# CAN.net
KiCad netlist of a schematic drawn in Altium Designer
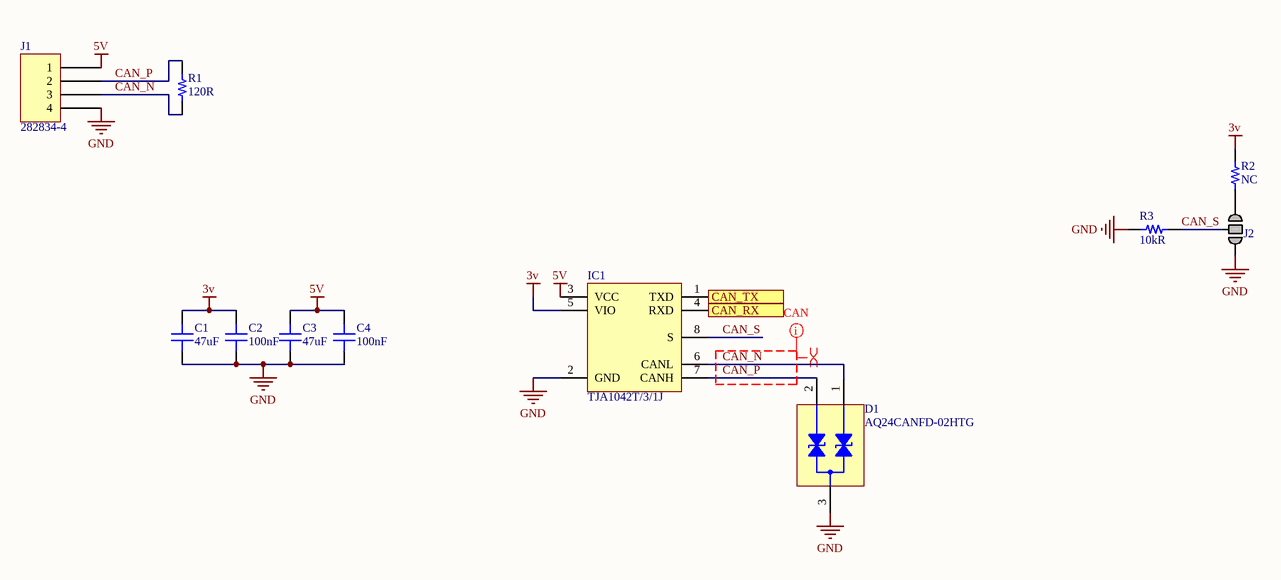
[diagram p0: CAN.SchDoc]

(export (version "E")
  (design (tool "Eeschema 10.0.6"))
  (components
    (comp (ref "C1")
      (value "47uF")
      (footprint "CAP 0603/1608")
      (description "Ceramic, SMT Capacitor")
      (fields
        (field (name "MANUFACTURER") "Murata")
        (field (name "MANUFACTURER PART NUMBER") "GRM188C80E476ME05D")
      )
      (libsource (lib "yildizIoT Library") (part "Capacitor - Ceramic"))
    )
    (comp (ref "C2")
      (value "100nF")
      (footprint "CAP 0603/1608")
      (description "Ceramic, SMT Capacitor")
      (fields
        (field (name "MANUFACTURER") "KEMET")
        (field (name "MANUFACTURER PART NUMBER") "C0603C104Z3VACTU")
      )
      (libsource (lib "yildizIoT Library") (part "Capacitor - Ceramic"))
    )
    (comp (ref "C3")
      (value "47uF")
      (footprint "CAP 0603/1608")
      (description "Ceramic, SMT Capacitor")
      (fields
        (field (name "MANUFACTURER") "Murata")
        (field (name "MANUFACTURER PART NUMBER") "GRM188C80E476ME05D")
      )
      (libsource (lib "yildizIoT Library") (part "Capacitor - Ceramic"))
    )
    (comp (ref "C4")
      (value "100nF")
      (footprint "CAP 0603/1608")
      (description "Ceramic, SMT Capacitor")
      (fields
        (field (name "MANUFACTURER") "KEMET")
        (field (name "MANUFACTURER PART NUMBER") "C0603C104Z3VACTU")
      )
      (libsource (lib "yildizIoT Library") (part "Capacitor - Ceramic"))
    )
    (comp (ref "D1")
      (value "AQ24CANFD-02HTG")
      (footprint "ON SEMI SOT-23-3")
      (description "TVS DIODE 24V 44V SOT23-3")
      (fields (field (name "MANUFACTURER") "Littelfuse"))
      (libsource (lib "Celestial Altium Library - altium_library") (part "ON SEMI SOT-23-3"))
    )
    (comp (ref "IC1")
      (value "TJA1042T/3/1J")
      (footprint "NXP SOIC-8")
      (description "High Speed CAN, CAN FD Transceiver")
      (fields (field (name "MANUFACTURER") "NXP Semiconductors"))
      (libsource (lib "yildizIoT Library") (part "NXP TJA1042T_3_1J"))
    )
    (comp (ref "J1")
      (value "282834-4")
      (footprint "TE 282834-4")
      (description "TERM BLK 4P SIDE ENT 2.54MM PCB")
      (fields (field (name "MANUFACTURER") "TE Connectivity AMP Connectors") (field (name "VOLTAGE") "150V"))
      (libsource (lib "Celestial Altium Library - altium_library") (part "4 Pin"))
    )
    (comp (ref "J2")
      (value "~")
      (footprint "jump_3way")
      (description "Selectable jumber")
      (libsource (lib "Muhammet_All_In_One") (part "JUMPER"))
    )
    (comp (ref "R1")
      (value "120R")
      (footprint "RES 0603/1608")
      (description "Ceramic, SMT Capacitor")
      (fields
        (field (name "MANUFACTURER") "Susumu")
        (field (name "MANUFACTURER PART NUMBER") "RR0816P-121-D")
      )
      (libsource (lib "yildizIoT Library") (part "Resistor_Chip"))
    )
    (comp (ref "R2")
      (value "NC")
      (footprint "RES 0603/1608")
      (description "Ceramic, SMT Capacitor")
      (libsource (lib "yildizIoT Library") (part "Resistor_Chip"))
    )
    (comp (ref "R3")
      (value "10kR")
      (footprint "RES 0603/1608")
      (description "Ceramic, SMT Capacitor")
      (fields
        (field (name "MANUFACTURER") "Stackpole Electronics")
        (field (name "MANUFACTURER PART NUMBER") "RNCP0603FTD10K0")
      )
      (libsource (lib "yildizIoT Library") (part "Resistor_Chip"))
    )
  )
  (nets
    (net (code "1") (name "/CAN_N") (class "Default")
      (node (ref "D1") (pin "1") (pinfunction "I/O_1_1") (pintype "passive"))
      (node (ref "IC1") (pin "6") (pinfunction "CANL_6") (pintype "passive"))
      (node (ref "J1") (pin "3") (pinfunction "3_3") (pintype "passive"))
      (node (ref "R1") (pin "1") (pinfunction "1_1") (pintype "passive"))
    )
    (net (code "2") (name "/CAN_P") (class "Default")
      (node (ref "D1") (pin "2") (pinfunction "GND_2") (pintype "passive"))
      (node (ref "IC1") (pin "7") (pinfunction "CANH_7") (pintype "passive"))
      (node (ref "J1") (pin "2") (pinfunction "2_2") (pintype "passive"))
      (node (ref "R1") (pin "2") (pinfunction "2_2") (pintype "passive"))
    )
    (net (code "3") (name "/CAN_RX") (class "Default")
      (node (ref "IC1") (pin "4") (pinfunction "RXD_4") (pintype "passive"))
    )
    (net (code "4") (name "/CAN_S") (class "Default")
      (node (ref "IC1") (pin "8") (pinfunction "S_8") (pintype "passive"))
      (node (ref "J2") (pin "2") (pinfunction "2_2") (pintype "passive"))
      (node (ref "R3") (pin "2") (pinfunction "2_2") (pintype "passive"))
    )
    (net (code "5") (name "/CAN_TX") (class "Default")
      (node (ref "IC1") (pin "1") (pinfunction "TXD_1") (pintype "passive"))
    )
    (net (code "6") (name "3v") (class "Default")
      (node (ref "C1") (pin "2") (pinfunction "2_2") (pintype "passive"))
      (node (ref "C2") (pin "2") (pinfunction "2_2") (pintype "passive"))
      (node (ref "IC1") (pin "5") (pinfunction "VIO_5") (pintype "passive"))
      (node (ref "R2") (pin "1") (pinfunction "1_1") (pintype "passive"))
    )
    (net (code "7") (name "5V") (class "Default")
      (node (ref "C3") (pin "2") (pinfunction "2_2") (pintype "passive"))
      (node (ref "C4") (pin "2") (pinfunction "2_2") (pintype "passive"))
      (node (ref "IC1") (pin "3") (pinfunction "VCC_3") (pintype "passive"))
      (node (ref "J1") (pin "1") (pinfunction "1_1") (pintype "passive"))
    )
    (net (code "8") (name "GND") (class "Default")
      (node (ref "C1") (pin "1") (pinfunction "1_1") (pintype "passive"))
      (node (ref "C2") (pin "1") (pinfunction "1_1") (pintype "passive"))
      (node (ref "C3") (pin "1") (pinfunction "1_1") (pintype "passive"))
      (node (ref "C4") (pin "1") (pinfunction "1_1") (pintype "passive"))
      (node (ref "D1") (pin "3") (pinfunction "I/O_2_3") (pintype "passive"))
      (node (ref "IC1") (pin "2") (pinfunction "GND_2") (pintype "passive"))
      (node (ref "J1") (pin "4") (pinfunction "4_4") (pintype "passive"))
      (node (ref "J2") (pin "3") (pinfunction "3_3") (pintype "passive"))
      (node (ref "R3") (pin "1") (pinfunction "1_1") (pintype "passive"))
    )
    (net (code "9") (name "Net-(J2-Pad1)") (class "Default")
      (node (ref "J2") (pin "1") (pinfunction "1_1") (pintype "passive"))
      (node (ref "R2") (pin "2") (pinfunction "2_2") (pintype "passive"))
    )
  )
)
